# module_1_LIGHT.net
KiCad netlist of a schematic drawn in Altium Designer
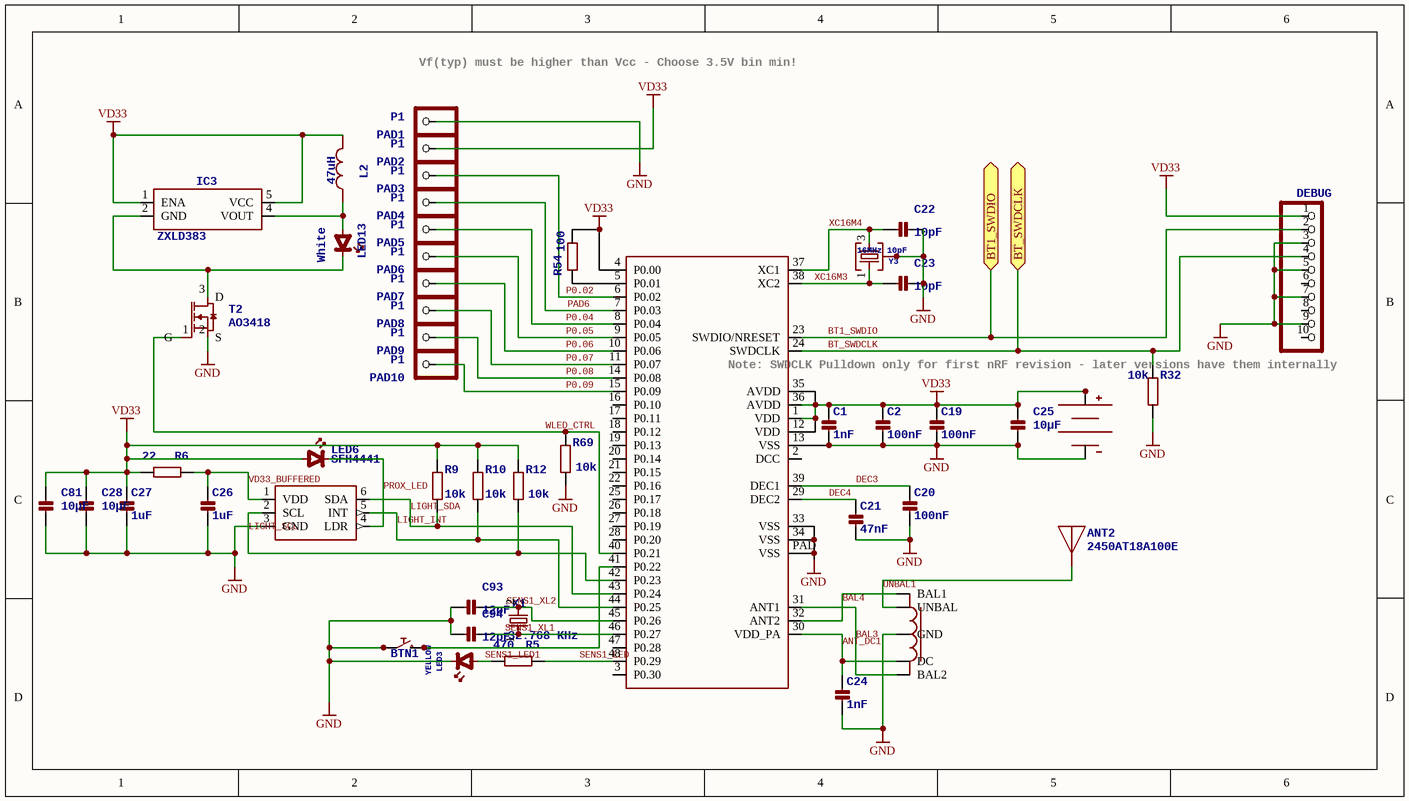
[diagram p0: module 1_LIGHT.SchDoc]

(export (version "E")
  (design (tool "Eeschema 10.0.6"))
  (components
    (comp (ref "ANT2")
      (value "2450AT18A100E")
      (footprint "1206_MINIMELF_COMBO")
      (description "2.45 GHz Antenna")
      (libsource (lib "WunderBar_v101") (part "ANTENNA_MONOPOLE1206"))
    )
    (comp (ref "BALUN1")
      (value "2450BM14A0002T")
      (footprint "6-PIN-0603")
      (description "2.45 GHz Impedance Matched Balun-Filter")
      (libsource (lib "WunderBar_v101") (part "BALUN"))
    )
    (comp (ref "BAT1")
      (value "BATTERYBK-912")
      (footprint "BK-912")
      (description "Coin battery holder")
      (libsource (lib "WunderBar_v101") (part "BATTERYBK-912"))
    )
    (comp (ref "BT1")
      (value "NRF51822QFN48")
      (footprint "QFN48_EP")
      (description "Nordic Bluetooth 4.0 low energy modul")
      (libsource (lib "WunderBar_v101") (part "NRF51822QFN48"))
    )
    (comp (ref "BTN1")
      (value "Tact Sw 4.6x2.8")
      (footprint "CK-KMR2")
      (description "Push button")
      (libsource (lib "WunderBar_v101") (part "PUSHBUTTONKMR2XX"))
    )
    (comp (ref "C1")
      (value "1nF")
      (footprint "0402")
      (description "Ceramic Capacitor")
      (libsource (lib "WunderBar_v101") (part "CAP_CERAMIC0402"))
    )
    (comp (ref "C2")
      (value "100nF")
      (footprint "0402")
      (description "Ceramic Capacitor")
      (libsource (lib "WunderBar_v101") (part "CAP_CERAMIC0402"))
    )
    (comp (ref "C19")
      (value "100nF")
      (footprint "0402")
      (description "Ceramic Capacitor")
      (libsource (lib "WunderBar_v101") (part "CAP_CERAMIC0402"))
    )
    (comp (ref "C20")
      (value "100nF")
      (footprint "0402")
      (description "Ceramic Capacitor")
      (libsource (lib "WunderBar_v101") (part "CAP_CERAMIC0402"))
    )
    (comp (ref "C21")
      (value "47nF")
      (footprint "0402")
      (description "Ceramic Capacitor")
      (libsource (lib "WunderBar_v101") (part "CAP_CERAMIC0402"))
    )
    (comp (ref "C22")
      (value "10pF")
      (footprint "0402")
      (description "Ceramic Capacitor")
      (libsource (lib "") (part "CAP_CERAMIC0402_1"))
    )
    (comp (ref "C23")
      (value "10pF")
      (footprint "0402")
      (description "Ceramic Capacitor")
      (libsource (lib "") (part "CAP_CERAMIC0402_1"))
    )
    (comp (ref "C24")
      (value "1nF")
      (footprint "0402")
      (description "Ceramic Capacitor")
      (libsource (lib "WunderBar_v101") (part "CAP_CERAMIC0402"))
    )
    (comp (ref "C25")
      (value "10µF")
      (footprint "0603")
      (description "Ceramic Capacitor")
      (libsource (lib "WunderBar_v101") (part "CAP_CERAMIC0603"))
    )
    (comp (ref "C26")
      (value "1uF")
      (footprint "0402")
      (description "Ceramic Capacitor")
      (libsource (lib "WunderBar_v101") (part "CAP_CERAMIC0402"))
    )
    (comp (ref "C27")
      (value "1uF")
      (footprint "0402")
      (description "Ceramic Capacitor")
      (libsource (lib "WunderBar_v101") (part "CAP_CERAMIC0402"))
    )
    (comp (ref "C28")
      (value "10µF")
      (footprint "0603")
      (description "Ceramic Capacitor")
      (libsource (lib "WunderBar_v101") (part "CAP_CERAMIC0603"))
    )
    (comp (ref "C81")
      (value "10µF")
      (footprint "0603")
      (description "Ceramic Capacitor")
      (libsource (lib "WunderBar_v101") (part "CAP_CERAMIC0603"))
    )
    (comp (ref "C93")
      (value "12pF")
      (footprint "0402")
      (description "Ceramic Capacitor")
      (libsource (lib "") (part "CAP_CERAMIC0402_1"))
    )
    (comp (ref "C94")
      (value "12pF")
      (footprint "0402")
      (description "Ceramic Capacitor")
      (libsource (lib "") (part "CAP_CERAMIC0402_1"))
    )
    (comp (ref "DEBUG1")
      (value "DEBUG")
      (footprint "2X05_SMT")
      (description "cortex DEBUG connector")
      (libsource (lib "WunderBar_v101") (part "HEADER-2X5SMD-1.27MM"))
    )
    (comp (ref "IC3")
      (value "ZXLD383")
      (footprint "SOT-23-5")
      (description "Diodes Inc. boost LED driver")
      (libsource (lib "WunderBar_v101") (part "ZXLD383SOT23-5"))
    )
    (comp (ref "L2")
      (value "47uH")
      (footprint "0805_MICROMELF_COMBO")
      (description "Inductor")
      (libsource (lib "WunderBar_v101") (part "INDUCTOR0805"))
    )
    (comp (ref "LED3")
      (value "YELLOW")
      (footprint "0402_POLAR")
      (description "LED common")
      (libsource (lib "WunderBar_v101") (part "LED0402"))
    )
    (comp (ref "LED6")
      (value "SFH4441")
      (footprint "MIDLED")
      (description "LED IR emitter 950NM")
      (libsource (lib "WunderBar_v101") (part "LEDMIDLED"))
    )
    (comp (ref "LED13")
      (value "White")
      (footprint "LED3X2")
      (description "LED common")
      (libsource (lib "WunderBar_v101") (part "LED3X2"))
    )
    (comp (ref "PAD1")
      (value "P1")
      (footprint "PCB_MEDIUM_RECT_PAD")
      (description "<b>PIN HEADER</b>")
      (libsource (lib "WunderBar_v101") (part "HEADER-1X1SMD_MEDIUM"))
    )
    (comp (ref "PAD2")
      (value "P1")
      (footprint "PCB_MEDIUM_RECT_PAD")
      (description "<b>PIN HEADER</b>")
      (libsource (lib "WunderBar_v101") (part "HEADER-1X1SMD_MEDIUM"))
    )
    (comp (ref "PAD3")
      (value "P1")
      (footprint "PCB_MEDIUM_RECT_PAD")
      (description "<b>PIN HEADER</b>")
      (libsource (lib "WunderBar_v101") (part "HEADER-1X1SMD_MEDIUM"))
    )
    (comp (ref "PAD4")
      (value "P1")
      (footprint "PCB_MEDIUM_RECT_PAD")
      (description "<b>PIN HEADER</b>")
      (libsource (lib "WunderBar_v101") (part "HEADER-1X1SMD_MEDIUM"))
    )
    (comp (ref "PAD5")
      (value "P1")
      (footprint "PCB_MEDIUM_RECT_PAD")
      (description "<b>PIN HEADER</b>")
      (libsource (lib "WunderBar_v101") (part "HEADER-1X1SMD_MEDIUM"))
    )
    (comp (ref "PAD6")
      (value "P1")
      (footprint "PCB_MEDIUM_RECT_PAD")
      (description "<b>PIN HEADER</b>")
      (libsource (lib "WunderBar_v101") (part "HEADER-1X1SMD_MEDIUM"))
    )
    (comp (ref "PAD7")
      (value "P1")
      (footprint "PCB_MEDIUM_RECT_PAD")
      (description "<b>PIN HEADER</b>")
      (libsource (lib "WunderBar_v101") (part "HEADER-1X1SMD_MEDIUM"))
    )
    (comp (ref "PAD8")
      (value "P1")
      (footprint "PCB_MEDIUM_RECT_PAD")
      (description "<b>PIN HEADER</b>")
      (libsource (lib "WunderBar_v101") (part "HEADER-1X1SMD_MEDIUM"))
    )
    (comp (ref "PAD9")
      (value "P1")
      (footprint "PCB_MEDIUM_RECT_PAD")
      (description "<b>PIN HEADER</b>")
      (libsource (lib "WunderBar_v101") (part "HEADER-1X1SMD_MEDIUM"))
    )
    (comp (ref "PAD10")
      (value "P1")
      (footprint "PCB_MEDIUM_RECT_PAD")
      (description "<b>PIN HEADER</b>")
      (libsource (lib "WunderBar_v101") (part "HEADER-1X1SMD_MEDIUM"))
    )
    (comp (ref "R5")
      (value "470")
      (footprint "0402")
      (description "RESISTOR")
      (libsource (lib "WunderBar_v101") (part "R-EU_0402"))
    )
    (comp (ref "R6")
      (value "22")
      (footprint "0402")
      (description "RESISTOR")
      (libsource (lib "WunderBar_v101") (part "R-EU_0402"))
    )
    (comp (ref "R9")
      (value "10k")
      (footprint "0402")
      (description "RESISTOR")
      (libsource (lib "WunderBar_v101") (part "R-EU_0402"))
    )
    (comp (ref "R10")
      (value "10k")
      (footprint "0402")
      (description "RESISTOR")
      (libsource (lib "WunderBar_v101") (part "R-EU_0402"))
    )
    (comp (ref "R12")
      (value "10k")
      (footprint "0402")
      (description "RESISTOR")
      (libsource (lib "WunderBar_v101") (part "R-EU_0402"))
    )
    (comp (ref "R32")
      (value "10k")
      (footprint "0402")
      (description "RESISTOR")
      (libsource (lib "WunderBar_v101") (part "R-EU_0402"))
    )
    (comp (ref "R54")
      (value "100")
      (footprint "0402")
      (description "RESISTOR")
      (libsource (lib "WunderBar_v101") (part "R-EU_0402"))
    )
    (comp (ref "R69")
      (value "10k")
      (footprint "0402")
      (description "RESISTOR")
      (libsource (lib "WunderBar_v101") (part "R-EU_0402"))
    )
    (comp (ref "SENSE3")
      (value "TCS37717FN")
      (footprint "DFN-6-0.65")
      (description "TAOS/ams color/light/proximity sensor")
      (libsource (lib "WunderBar_v101") (part "TCS3771"))
    )
    (comp (ref "T2")
      (value "AO3418")
      (footprint "SOT23")
      (description "N-Channel MOSFET, enhancement mode")
      (libsource (lib "WunderBar_v101") (part "NMOS_ENH"))
    )
    (comp (ref "X1")
      (value "32.768 KHz")
      (footprint "1206_MINIMELF_COMBO")
      (description "CL05C120JB5")
      (libsource (lib "WunderBar_v101") (part "CRYSTAL1206"))
    )
    (comp (ref "Y3")
      (value "16MHz 10pF")
      (footprint "CRYSTAL25X20")
      (description "16MHz crystal 2.5x2mm")
      (libsource (lib "WunderBar_v101") (part "CRYSTAL_WITH_GROUND25X20"))
    )
  )
  (nets
    (net (code "1") (name "/ANT_DC1") (class "Default")
      (node (ref "BALUN1") (pin "5") (pinfunction "DC_5") (pintype "power_in"))
      (node (ref "BT1") (pin "30") (pinfunction "VDD_PA_30") (pintype "passive"))
      (node (ref "C24") (pin "1") (pinfunction "1_1") (pintype "passive"))
    )
    (net (code "2") (name "/BAL3") (class "Default")
      (node (ref "BALUN1") (pin "4") (pinfunction "BAL2_4") (pintype "passive"))
      (node (ref "BT1") (pin "31") (pinfunction "ANT1_31") (pintype "passive"))
    )
    (net (code "3") (name "/BAL4") (class "Default")
      (node (ref "BALUN1") (pin "3") (pinfunction "BAL1_3") (pintype "passive"))
      (node (ref "BT1") (pin "32") (pinfunction "ANT2_32") (pintype "passive"))
    )
    (net (code "4") (name "/BT1_SWDIO") (class "Default")
      (node (ref "BT1") (pin "23") (pinfunction "SWDIO/NRESET_23") (pintype "passive"))
      (node (ref "DEBUG1") (pin "2") (pinfunction "2_2") (pintype "passive"))
    )
    (net (code "5") (name "/BT_SWDCLK") (class "Default")
      (node (ref "BT1") (pin "24") (pinfunction "SWDCLK_24") (pintype "passive"))
      (node (ref "DEBUG1") (pin "4") (pinfunction "4_4") (pintype "passive"))
      (node (ref "R32") (pin "2") (pinfunction "2_2") (pintype "passive"))
    )
    (net (code "6") (name "/DEC3") (class "Default")
      (node (ref "BT1") (pin "39") (pinfunction "DEC1_39") (pintype "passive"))
      (node (ref "C20") (pin "1") (pinfunction "1_1") (pintype "passive"))
    )
    (net (code "7") (name "/DEC4") (class "Default")
      (node (ref "BT1") (pin "29") (pinfunction "DEC2_29") (pintype "passive"))
      (node (ref "C21") (pin "1") (pinfunction "1_1") (pintype "passive"))
    )
    (net (code "8") (name "/LIGHT_INT") (class "Default")
      (node (ref "BT1") (pin "44") (pinfunction "P0.25_44") (pintype "passive"))
      (node (ref "R10") (pin "1") (pinfunction "1_1") (pintype "passive"))
      (node (ref "SENSE3") (pin "5") (pinfunction "INT_5") (pintype "output"))
    )
    (net (code "9") (name "/LIGHT_SCL") (class "Default")
      (node (ref "BT1") (pin "42") (pinfunction "P0.23_42") (pintype "passive"))
      (node (ref "R12") (pin "1") (pinfunction "1_1") (pintype "passive"))
      (node (ref "SENSE3") (pin "2") (pinfunction "SCL_2") (pintype "passive"))
    )
    (net (code "10") (name "/LIGHT_SDA") (class "Default")
      (node (ref "BT1") (pin "43") (pinfunction "P0.24_43") (pintype "passive"))
      (node (ref "R9") (pin "1") (pinfunction "1_1") (pintype "passive"))
      (node (ref "SENSE3") (pin "6") (pinfunction "SDA_6") (pintype "passive"))
    )
    (net (code "11") (name "/P0.02") (class "Default")
      (node (ref "BT1") (pin "6") (pinfunction "P0.02_6") (pintype "passive"))
      (node (ref "PAD3") (pin "1") (pinfunction "1_1") (pintype "passive"))
    )
    (net (code "12") (name "/P0.04") (class "Default")
      (node (ref "BT1") (pin "8") (pinfunction "P0.04_8") (pintype "passive"))
      (node (ref "PAD5") (pin "1") (pinfunction "1_1") (pintype "passive"))
    )
    (net (code "13") (name "/P0.05") (class "Default")
      (node (ref "BT1") (pin "9") (pinfunction "P0.05_9") (pintype "passive"))
      (node (ref "PAD6") (pin "1") (pinfunction "1_1") (pintype "passive"))
    )
    (net (code "14") (name "/P0.06") (class "Default")
      (node (ref "BT1") (pin "10") (pinfunction "P0.06_10") (pintype "passive"))
      (node (ref "PAD7") (pin "1") (pinfunction "1_1") (pintype "passive"))
    )
    (net (code "15") (name "/P0.07") (class "Default")
      (node (ref "BT1") (pin "11") (pinfunction "P0.07_11") (pintype "passive"))
      (node (ref "PAD8") (pin "1") (pinfunction "1_1") (pintype "passive"))
    )
    (net (code "16") (name "/P0.08") (class "Default")
      (node (ref "BT1") (pin "14") (pinfunction "P0.08_14") (pintype "passive"))
      (node (ref "PAD9") (pin "1") (pinfunction "1_1") (pintype "passive"))
    )
    (net (code "17") (name "/P0.09") (class "Default")
      (node (ref "BT1") (pin "15") (pinfunction "P0.09_15") (pintype "passive"))
      (node (ref "PAD10") (pin "1") (pinfunction "1_1") (pintype "passive"))
    )
    (net (code "18") (name "/PAD6") (class "Default")
      (node (ref "BT1") (pin "7") (pinfunction "P0.03_7") (pintype "passive"))
      (node (ref "PAD4") (pin "1") (pinfunction "1_1") (pintype "passive"))
    )
    (net (code "19") (name "/PROX_LED") (class "Default")
      (node (ref "LED6") (pin "C") (pinfunction "CATHODE_C") (pintype "passive"))
      (node (ref "SENSE3") (pin "4") (pinfunction "LDR_4") (pintype "output"))
    )
    (net (code "20") (name "/SENS1_LED") (class "Default")
      (node (ref "BT1") (pin "48") (pinfunction "P0.29_48") (pintype "passive"))
      (node (ref "R5") (pin "1") (pinfunction "1_1") (pintype "passive"))
    )
    (net (code "21") (name "/SENS1_LED1") (class "Default")
      (node (ref "LED3") (pin "A") (pinfunction "ANODE_A") (pintype "passive"))
      (node (ref "R5") (pin "2") (pinfunction "2_2") (pintype "passive"))
    )
    (net (code "22") (name "/SENS1_XL1") (class "Default")
      (node (ref "BT1") (pin "46") (pinfunction "P0.27_46") (pintype "passive"))
      (node (ref "C94") (pin "2") (pinfunction "2_2") (pintype "passive"))
      (node (ref "X1") (pin "1") (pinfunction "1_1") (pintype "passive"))
    )
    (net (code "23") (name "/SENS1_XL2") (class "Default")
      (node (ref "BT1") (pin "45") (pinfunction "P0.26_45") (pintype "passive"))
      (node (ref "C93") (pin "2") (pinfunction "2_2") (pintype "passive"))
      (node (ref "X1") (pin "2") (pinfunction "2_2") (pintype "passive"))
    )
    (net (code "24") (name "/UNBAL1") (class "Default")
      (node (ref "ANT2") (pin "1") (pinfunction "ANT_1") (pintype "passive"))
      (node (ref "BALUN1") (pin "1") (pinfunction "UNBAL_1") (pintype "passive"))
    )
    (net (code "25") (name "/VD33_BUFFERED") (class "Default")
      (node (ref "C26") (pin "1") (pinfunction "1_1") (pintype "passive"))
      (node (ref "R6") (pin "2") (pinfunction "2_2") (pintype "passive"))
      (node (ref "SENSE3") (pin "1") (pinfunction "VDD_1") (pintype "power_in"))
    )
    (net (code "26") (name "/WLED_CTRL") (class "Default")
      (node (ref "BT1") (pin "40") (pinfunction "P0.21_40") (pintype "passive"))
      (node (ref "R69") (pin "2") (pinfunction "2_2") (pintype "passive"))
      (node (ref "T2") (pin "1") (pinfunction "G_1") (pintype "passive"))
    )
    (net (code "27") (name "/XC16M3") (class "Default")
      (node (ref "BT1") (pin "38") (pinfunction "XC2_38") (pintype "passive"))
      (node (ref "C23") (pin "1") (pinfunction "1_1") (pintype "passive"))
      (node (ref "Y3") (pin "1") (pinfunction "1_1") (pintype "passive"))
    )
    (net (code "28") (name "/XC16M4") (class "Default")
      (node (ref "BT1") (pin "37") (pinfunction "XC1_37") (pintype "passive"))
      (node (ref "C22") (pin "1") (pinfunction "1_1") (pintype "passive"))
      (node (ref "Y3") (pin "3") (pinfunction "3_3") (pintype "passive"))
    )
    (net (code "29") (name "GND") (class "Default")
      (node (ref "BALUN1") (pin "2") (pinfunction "GND_2") (pintype "power_in"))
      (node (ref "BAT1") (pin "-") (pinfunction "-_-") (pintype "power_in"))
      (node (ref "BT1") (pin "13") (pinfunction "VSS_13") (pintype "passive"))
      (node (ref "BT1") (pin "33") (pinfunction "VSS_33") (pintype "passive"))
      (node (ref "BT1") (pin "34") (pinfunction "VSS_34") (pintype "passive"))
      (node (ref "BT1") (pin "PAD") (pinfunction "VSS_PAD") (pintype "passive"))
      (node (ref "BTN1") (pin "P1") (pinfunction "1_P1") (pintype "passive"))
      (node (ref "BTN1") (pin "P2") (pinfunction "2_P2") (pintype "passive"))
      (node (ref "C1") (pin "2") (pinfunction "2_2") (pintype "passive"))
      (node (ref "C19") (pin "2") (pinfunction "2_2") (pintype "passive"))
      (node (ref "C2") (pin "2") (pinfunction "2_2") (pintype "passive"))
      (node (ref "C20") (pin "2") (pinfunction "2_2") (pintype "passive"))
      (node (ref "C21") (pin "2") (pinfunction "2_2") (pintype "passive"))
      (node (ref "C22") (pin "2") (pinfunction "2_2") (pintype "passive"))
      (node (ref "C23") (pin "2") (pinfunction "2_2") (pintype "passive"))
      (node (ref "C24") (pin "2") (pinfunction "2_2") (pintype "passive"))
      (node (ref "C25") (pin "2") (pinfunction "P2_2") (pintype "passive"))
      (node (ref "C26") (pin "2") (pinfunction "2_2") (pintype "passive"))
      (node (ref "C27") (pin "2") (pinfunction "2_2") (pintype "passive"))
      (node (ref "C28") (pin "2") (pinfunction "P2_2") (pintype "passive"))
      (node (ref "C81") (pin "2") (pinfunction "P2_2") (pintype "passive"))
      (node (ref "C93") (pin "1") (pinfunction "1_1") (pintype "passive"))
      (node (ref "C94") (pin "1") (pinfunction "1_1") (pintype "passive"))
      (node (ref "DEBUG1") (pin "3") (pinfunction "3_3") (pintype "passive"))
      (node (ref "DEBUG1") (pin "5") (pinfunction "5_5") (pintype "passive"))
      (node (ref "DEBUG1") (pin "7") (pinfunction "7_7") (pintype "passive"))
      (node (ref "DEBUG1") (pin "9") (pinfunction "9_9") (pintype "passive"))
      (node (ref "LED3") (pin "K") (pinfunction "CATHODE_K") (pintype "passive"))
      (node (ref "PAD1") (pin "1") (pinfunction "1_1") (pintype "passive"))
      (node (ref "R32") (pin "1") (pinfunction "1_1") (pintype "passive"))
      (node (ref "R69") (pin "1") (pinfunction "1_1") (pintype "passive"))
      (node (ref "SENSE3") (pin "3") (pinfunction "GND_3") (pintype "power_in"))
      (node (ref "T2") (pin "2") (pinfunction "S_2") (pintype "passive"))
      (node (ref "Y3") (pin "2") (pinfunction "2_2") (pintype "power_in"))
      (node (ref "Y3") (pin "4") (pinfunction "4_4") (pintype "power_in"))
    )
    (net (code "30") (name "Net-(BT1-P0.01)") (class "Default")
      (node (ref "BT1") (pin "5") (pinfunction "P0.01_5") (pintype "passive"))
      (node (ref "R54") (pin "2") (pinfunction "2_2") (pintype "passive"))
    )
    (net (code "31") (name "Net-(BT1-P0.22)") (class "Default")
      (node (ref "BT1") (pin "41") (pinfunction "P0.22_41") (pintype "passive"))
      (node (ref "BTN1") (pin "P3") (pinfunction "3_P3") (pintype "passive"))
      (node (ref "BTN1") (pin "P4") (pinfunction "4_P4") (pintype "passive"))
    )
    (net (code "32") (name "Net-(IC3-GND)") (class "Default")
      (node (ref "IC3") (pin "2") (pinfunction "GND_2") (pintype "passive"))
      (node (ref "LED13") (pin "K") (pinfunction "CATHODE_K") (pintype "passive"))
      (node (ref "T2") (pin "3") (pinfunction "D_3") (pintype "passive"))
    )
    (net (code "33") (name "Net-(IC3-VOUT)") (class "Default")
      (node (ref "IC3") (pin "4") (pinfunction "VOUT_4") (pintype "passive"))
      (node (ref "L2") (pin "1") (pinfunction "1_1") (pintype "passive"))
      (node (ref "LED13") (pin "A") (pinfunction "ANODE_A") (pintype "passive"))
    )
    (net (code "34") (name "VD33") (class "Default")
      (node (ref "BAT1") (pin "+1") (pinfunction "+_+1") (pintype "power_in"))
      (node (ref "BAT1") (pin "+2") (pinfunction "+_+2") (pintype "power_in"))
      (node (ref "BT1") (pin "1") (pinfunction "VDD_1") (pintype "passive"))
      (node (ref "BT1") (pin "12") (pinfunction "VDD_12") (pintype "passive"))
      (node (ref "BT1") (pin "35") (pinfunction "AVDD_35") (pintype "passive"))
      (node (ref "BT1") (pin "36") (pinfunction "AVDD_36") (pintype "passive"))
      (node (ref "BT1") (pin "4") (pinfunction "P0.00_4") (pintype "passive"))
      (node (ref "C1") (pin "1") (pinfunction "1_1") (pintype "passive"))
      (node (ref "C19") (pin "1") (pinfunction "1_1") (pintype "passive"))
      (node (ref "C2") (pin "1") (pinfunction "1_1") (pintype "passive"))
      (node (ref "C25") (pin "1") (pinfunction "P1_1") (pintype "passive"))
      (node (ref "C27") (pin "1") (pinfunction "1_1") (pintype "passive"))
      (node (ref "C28") (pin "1") (pinfunction "P1_1") (pintype "passive"))
      (node (ref "C81") (pin "1") (pinfunction "P1_1") (pintype "passive"))
      (node (ref "DEBUG1") (pin "1") (pinfunction "1_1") (pintype "passive"))
      (node (ref "IC3") (pin "1") (pinfunction "ENA_1") (pintype "passive"))
      (node (ref "IC3") (pin "5") (pinfunction "VCC_5") (pintype "passive"))
      (node (ref "L2") (pin "2") (pinfunction "2_2") (pintype "passive"))
      (node (ref "LED6") (pin "A") (pinfunction "ANODE_A") (pintype "passive"))
      (node (ref "PAD2") (pin "1") (pinfunction "1_1") (pintype "passive"))
      (node (ref "R10") (pin "2") (pinfunction "2_2") (pintype "passive"))
      (node (ref "R12") (pin "2") (pinfunction "2_2") (pintype "passive"))
      (node (ref "R54") (pin "1") (pinfunction "1_1") (pintype "passive"))
      (node (ref "R6") (pin "1") (pinfunction "1_1") (pintype "passive"))
      (node (ref "R9") (pin "2") (pinfunction "2_2") (pintype "passive"))
    )
    (net (code "35") (name "unconnected-(BT1-DCC-Pad2)") (class "Default")
      (node (ref "BT1") (pin "2") (pinfunction "DCC_2") (pintype "passive"))
    )
    (net (code "36") (name "unconnected-(BT1-P0.10-Pad16)") (class "Default")
      (node (ref "BT1") (pin "16") (pinfunction "P0.10_16") (pintype "passive"))
    )
    (net (code "37") (name "unconnected-(BT1-P0.11-Pad17)") (class "Default")
      (node (ref "BT1") (pin "17") (pinfunction "P0.11_17") (pintype "passive"))
    )
    (net (code "38") (name "unconnected-(BT1-P0.12-Pad18)") (class "Default")
      (node (ref "BT1") (pin "18") (pinfunction "P0.12_18") (pintype "passive"))
    )
    (net (code "39") (name "unconnected-(BT1-P0.13-Pad19)") (class "Default")
      (node (ref "BT1") (pin "19") (pinfunction "P0.13_19") (pintype "passive"))
    )
    (net (code "40") (name "unconnected-(BT1-P0.14-Pad20)") (class "Default")
      (node (ref "BT1") (pin "20") (pinfunction "P0.14_20") (pintype "passive"))
    )
    (net (code "41") (name "unconnected-(BT1-P0.15-Pad21)") (class "Default")
      (node (ref "BT1") (pin "21") (pinfunction "P0.15_21") (pintype "passive"))
    )
    (net (code "42") (name "unconnected-(BT1-P0.16-Pad22)") (class "Default")
      (node (ref "BT1") (pin "22") (pinfunction "P0.16_22") (pintype "passive"))
    )
    (net (code "43") (name "unconnected-(BT1-P0.17-Pad25)") (class "Default")
      (node (ref "BT1") (pin "25") (pinfunction "P0.17_25") (pintype "passive"))
    )
    (net (code "44") (name "unconnected-(BT1-P0.18-Pad26)") (class "Default")
      (node (ref "BT1") (pin "26") (pinfunction "P0.18_26") (pintype "passive"))
    )
    (net (code "45") (name "unconnected-(BT1-P0.19-Pad27)") (class "Default")
      (node (ref "BT1") (pin "27") (pinfunction "P0.19_27") (pintype "passive"))
    )
    (net (code "46") (name "unconnected-(BT1-P0.20-Pad28)") (class "Default")
      (node (ref "BT1") (pin "28") (pinfunction "P0.20_28") (pintype "passive"))
    )
    (net (code "47") (name "unconnected-(BT1-P0.28-Pad47)") (class "Default")
      (node (ref "BT1") (pin "47") (pinfunction "P0.28_47") (pintype "passive"))
    )
    (net (code "48") (name "unconnected-(BT1-P0.30-Pad3)") (class "Default")
      (node (ref "BT1") (pin "3") (pinfunction "P0.30_3") (pintype "passive"))
    )
    (net (code "49") (name "unconnected-(DEBUG1-Pad6)") (class "Default")
      (node (ref "DEBUG1") (pin "6") (pinfunction "6_6") (pintype "passive"))
    )
    (net (code "50") (name "unconnected-(DEBUG1-Pad8)") (class "Default")
      (node (ref "DEBUG1") (pin "8") (pinfunction "8_8") (pintype "passive"))
    )
    (net (code "51") (name "unconnected-(DEBUG1-Pad10)") (class "Default")
      (node (ref "DEBUG1") (pin "10") (pinfunction "10_10") (pintype "passive"))
    )
  )
)
